# LCC_Terminator.net
KiCad netlist of a schematic drawn in Altium Designer
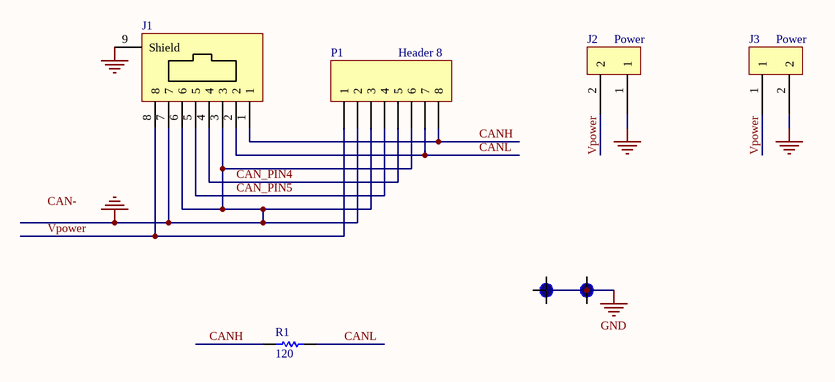
[diagram p0: LCC_Terminator.SchDoc]

(export (version "E")
  (design (tool "Eeschema 10.0.6"))
  (components
    (comp (ref "H3")
      (value "Hole")
      (footprint "Mounting Hole M3")
      (libsource (lib "Custom") (part "MountingHole"))
    )
    (comp (ref "H4")
      (value "Hole")
      (footprint "Mounting Hole M3")
      (libsource (lib "Custom") (part "MountingHole"))
    )
    (comp (ref "J1")
      (value "RJ45 Amphenol RJHSE-5380")
      (footprint "Amphenol RJHSE-5380")
      (libsource (lib "Custom") (part "RJ45"))
    )
    (comp (ref "J2")
      (value "Power")
      (footprint "0.156 SIP 2 PIN - R/A")
      (libsource (lib "") (part "SIP2 CONNECTOR_1"))
    )
    (comp (ref "J3")
      (value "Power")
      (footprint "DC 2.5mm PCB Jack")
      (libsource (lib "Custom") (part "SIP2 CONNECTOR"))
    )
    (comp (ref "P1")
      (value "Header 8")
      (footprint "HDR1X8")
      (description "Header, 8-Pin")
      (fields (field (name "PUBLISHER") "Altium Limited"))
      (libsource (lib "Miscellaneous Connectors") (part "Header 8"))
    )
    (comp (ref "R1")
      (value "120")
      (footprint "Resistor Axial 1/8W 0.4")
      (fields (field (name "Comment") "Res1"))
      (libsource (lib "Custom") (part "Resistor"))
    )
  )
  (nets
    (net (code "2") (name "/CANH") (class "Default")
      (node (ref "J1") (pin "1") (pinfunction "1_1") (pintype "passive"))
      (node (ref "P1") (pin "8") (pinfunction "8_8") (pintype "passive"))
      (node (ref "R1") (pin "1") (pinfunction "1_1") (pintype "passive"))
    )
    (net (code "3") (name "/CANL") (class "Default")
      (node (ref "J1") (pin "2") (pinfunction "2_2") (pintype "passive"))
      (node (ref "P1") (pin "7") (pinfunction "7_7") (pintype "passive"))
      (node (ref "R1") (pin "2") (pinfunction "2_2") (pintype "passive"))
    )
    (net (code "4") (name "/CAN_PIN4") (class "Default")
      (node (ref "J1") (pin "4") (pinfunction "4_4") (pintype "passive"))
      (node (ref "P1") (pin "5") (pinfunction "5_5") (pintype "passive"))
    )
    (net (code "5") (name "/CAN_PIN5") (class "Default")
      (node (ref "J1") (pin "5") (pinfunction "5_5") (pintype "passive"))
      (node (ref "P1") (pin "4") (pinfunction "4_4") (pintype "passive"))
    )
    (net (code "6") (name "/Vpower") (class "Default")
      (node (ref "J1") (pin "8") (pinfunction "8_8") (pintype "passive"))
      (node (ref "J2") (pin "2") (pinfunction "2_2") (pintype "passive"))
      (node (ref "J3") (pin "1") (pinfunction "1_1") (pintype "passive"))
      (node (ref "P1") (pin "1") (pinfunction "1_1") (pintype "passive"))
    )
    (net (code "7") (name "GND") (class "Default")
      (node (ref "H3") (pin "1") (pinfunction "GND_1") (pintype "passive"))
      (node (ref "H4") (pin "1") (pinfunction "GND_1") (pintype "passive"))
      (node (ref "J1") (pin "3") (pinfunction "3_3") (pintype "passive"))
      (node (ref "J1") (pin "6") (pinfunction "6_6") (pintype "passive"))
      (node (ref "J1") (pin "7") (pinfunction "7_7") (pintype "passive"))
      (node (ref "J1") (pin "9") (pinfunction "Shield_9") (pintype "passive"))
      (node (ref "J2") (pin "1") (pinfunction "1_1") (pintype "passive"))
      (node (ref "J3") (pin "2") (pinfunction "2_2") (pintype "passive"))
      (node (ref "P1") (pin "2") (pinfunction "2_2") (pintype "passive"))
      (node (ref "P1") (pin "3") (pinfunction "3_3") (pintype "passive"))
      (node (ref "P1") (pin "6") (pinfunction "6_6") (pintype "passive"))
    )
  )
)
